# PCB-2x8GPIO.net
KiCad netlist of a schematic drawn in EAGLE
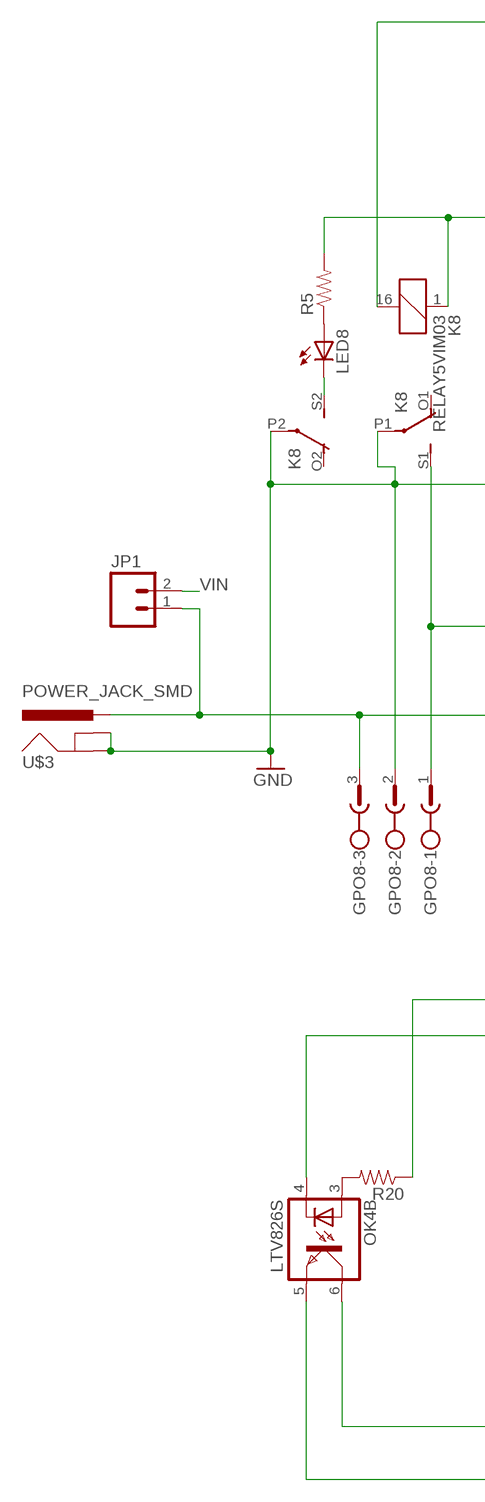
[diagram p0: schematic, sheet 1, part 1 of 2]
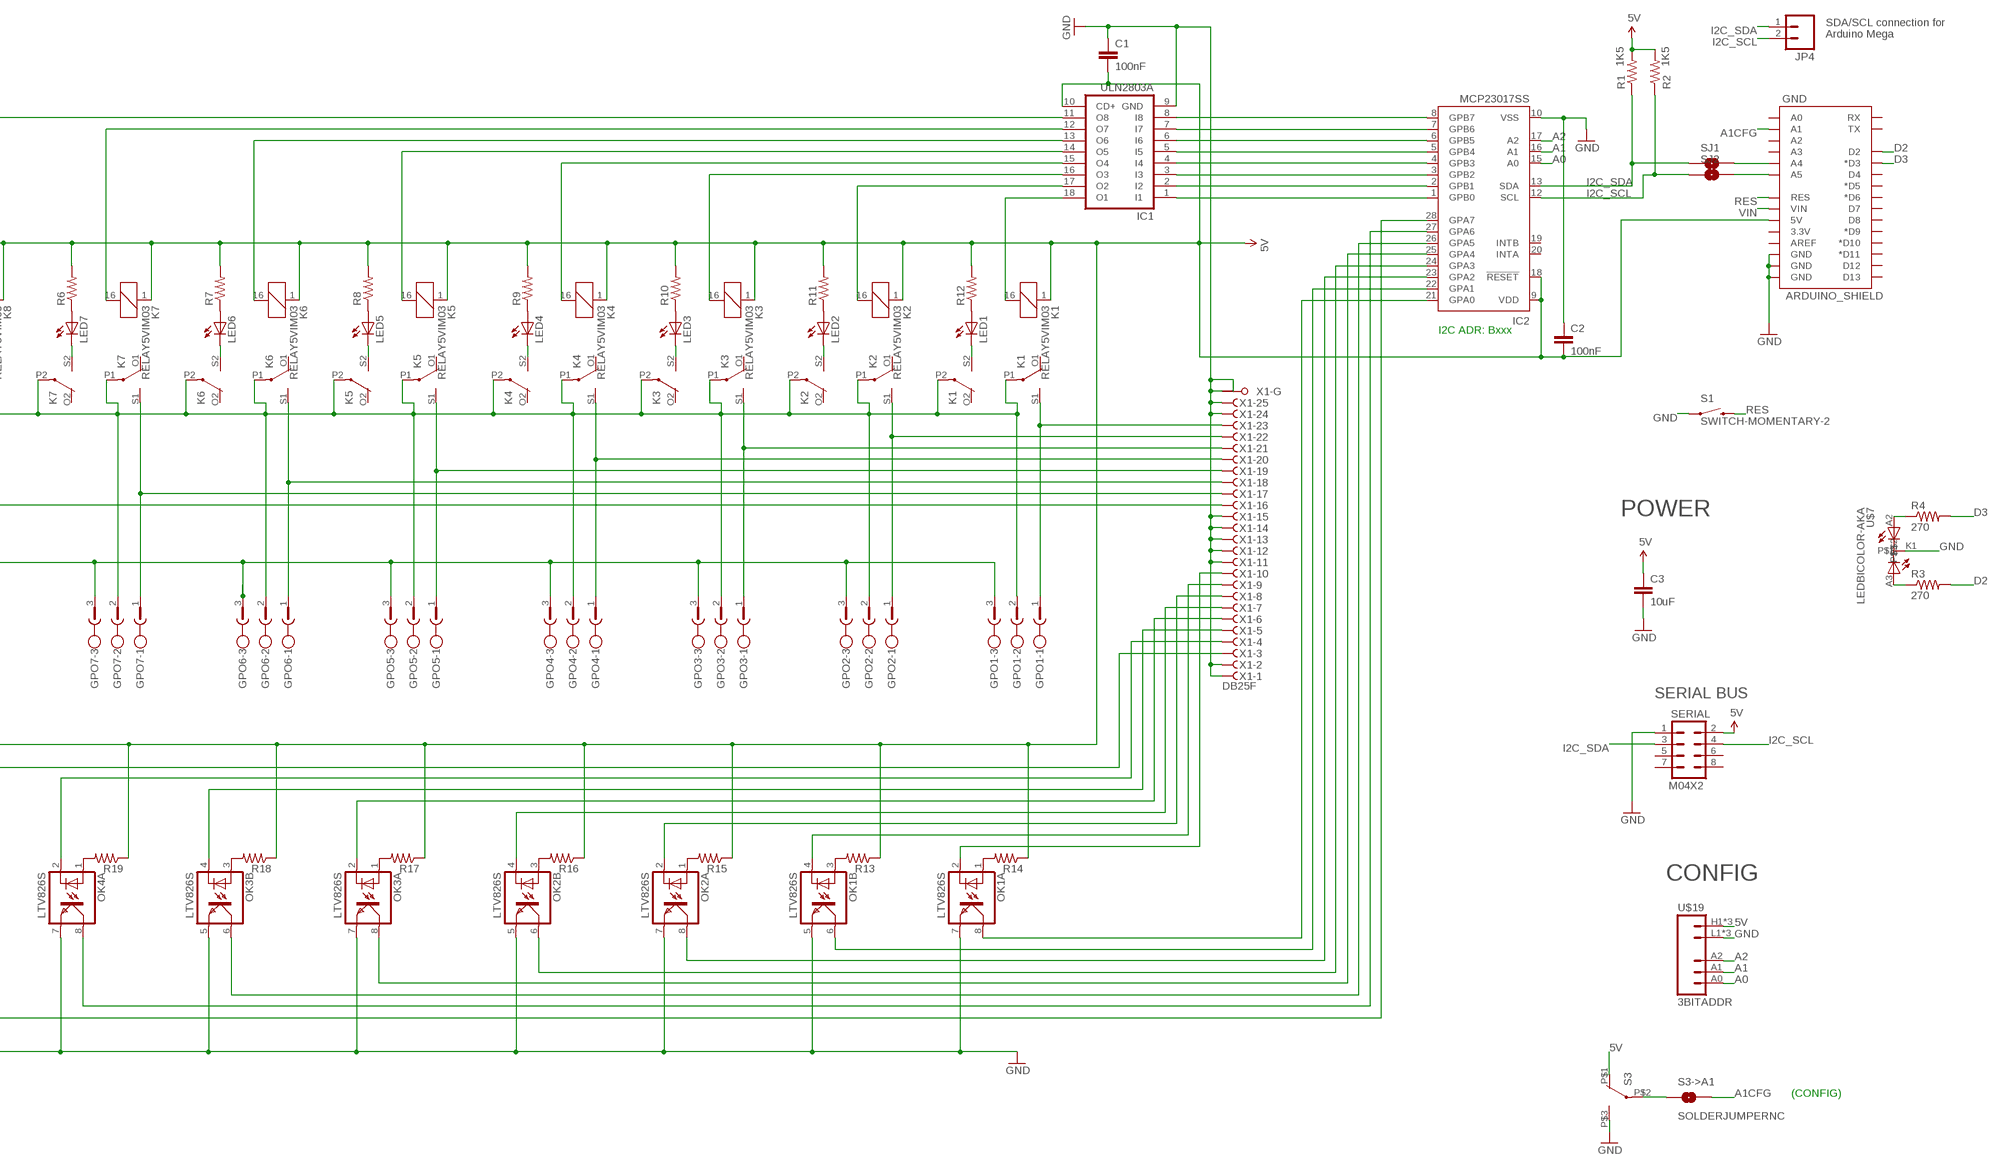
[diagram p1: schematic, sheet 1, part 2 of 2]

(export (version "E")
  (design (tool "Eeschema 10.0.6"))
  (components
    (comp (ref "C1")
      (value "100nF")
      (footprint "eagle-import:0805")
      (libsource (lib "eagle-import") (part "CAP0805"))
    )
    (comp (ref "C2")
      (value "100nF")
      (footprint "eagle-import:0603-CAP")
      (libsource (lib "eagle-import") (part "CAP0603-CAP"))
    )
    (comp (ref "C3")
      (value "10uF")
      (footprint "eagle-import:0805")
      (libsource (lib "eagle-import") (part "CAP0805"))
    )
    (comp (ref "GND")
      (value "ARDUINO_SHIELD")
      (footprint "eagle-import:ARDUINO_BOXSHIELD_NOHOLES")
      (libsource (lib "eagle-import") (part "ARDUINO_SHIELD"))
    )
    (comp (ref "GPO1")
      (value "CON1")
      (footprint "eagle-import:MSTBV3")
      (fields (field (name "MPN") "MSTBV 2,5/3-GF-5.08"))
      (libsource (lib "eagle-import") (part "MSTBV3"))
    )
    (comp (ref "GPO2")
      (value "CON1")
      (footprint "eagle-import:MSTBV3")
      (fields (field (name "MPN") "MSTBV 2,5/3-GF-5.08"))
      (libsource (lib "eagle-import") (part "MSTBV3"))
    )
    (comp (ref "GPO3")
      (value "CON1")
      (footprint "eagle-import:MSTBV3")
      (fields (field (name "MPN") "MSTBV 2,5/3-GF-5.08"))
      (libsource (lib "eagle-import") (part "MSTBV3"))
    )
    (comp (ref "GPO4")
      (value "CON1")
      (footprint "eagle-import:MSTBV3")
      (fields (field (name "MPN") "MSTBV 2,5/3-GF-5.08"))
      (libsource (lib "eagle-import") (part "MSTBV3"))
    )
    (comp (ref "GPO5")
      (value "CON1")
      (footprint "eagle-import:MSTBV3")
      (fields (field (name "MPN") "MSTBV 2,5/3-GF-5.08"))
      (libsource (lib "eagle-import") (part "MSTBV3"))
    )
    (comp (ref "GPO6")
      (value "CON1")
      (footprint "eagle-import:MSTBV3")
      (fields (field (name "MPN") "MSTBV 2,5/3-GF-5.08"))
      (libsource (lib "eagle-import") (part "MSTBV3"))
    )
    (comp (ref "GPO7")
      (value "CON1")
      (footprint "eagle-import:MSTBV3")
      (fields (field (name "MPN") "MSTBV 2,5/3-GF-5.08"))
      (libsource (lib "eagle-import") (part "MSTBV3"))
    )
    (comp (ref "GPO8")
      (value "GPO8")
      (footprint "eagle-import:MSTBV3")
      (fields (field (name "MPN") "MSTBV 2,5/3-GF-5.08"))
      (libsource (lib "eagle-import") (part "MSTBV3"))
    )
    (comp (ref "IC1")
      (value "ULN2803A")
      (footprint "eagle-import:SO18W")
      (libsource (lib "eagle-import") (part "ULN2803ASO18W"))
    )
    (comp (ref "IC2")
      (value "MCP23017SS")
      (footprint "eagle-import:SSOP28")
      (fields (field (name "MF") "MICROCHIP") (field (name "MPN") "MCP23017-E/SS"))
      (libsource (lib "eagle-import") (part "MCP23017SS"))
    )
    (comp (ref "JP1")
      (value "M02LOCK")
      (footprint "eagle-import:1X02_LOCK")
      (libsource (lib "eagle-import") (part "M02LOCK"))
    )
    (comp (ref "JP4")
      (value "M02PTH")
      (footprint "eagle-import:1X02")
      (libsource (lib "eagle-import") (part "M02PTH"))
    )
    (comp (ref "K1")
      (value "RELAY5VIM03")
      (footprint "eagle-import:DS2Y")
      (libsource (lib "eagle-import") (part "RELAY5VIM03"))
    )
    (comp (ref "K2")
      (value "RELAY5VIM03")
      (footprint "eagle-import:DS2Y")
      (libsource (lib "eagle-import") (part "RELAY5VIM03"))
    )
    (comp (ref "K3")
      (value "RELAY5VIM03")
      (footprint "eagle-import:DS2Y")
      (libsource (lib "eagle-import") (part "RELAY5VIM03"))
    )
    (comp (ref "K4")
      (value "RELAY5VIM03")
      (footprint "eagle-import:DS2Y")
      (libsource (lib "eagle-import") (part "RELAY5VIM03"))
    )
    (comp (ref "K5")
      (value "RELAY5VIM03")
      (footprint "eagle-import:DS2Y")
      (libsource (lib "eagle-import") (part "RELAY5VIM03"))
    )
    (comp (ref "K6")
      (value "RELAY5VIM03")
      (footprint "eagle-import:DS2Y")
      (libsource (lib "eagle-import") (part "RELAY5VIM03"))
    )
    (comp (ref "K7")
      (value "RELAY5VIM03")
      (footprint "eagle-import:DS2Y")
      (libsource (lib "eagle-import") (part "RELAY5VIM03"))
    )
    (comp (ref "K8")
      (value "RELAY5VIM03")
      (footprint "eagle-import:DS2Y")
      (libsource (lib "eagle-import") (part "RELAY5VIM03"))
    )
    (comp (ref "LED1")
      (value "LED0603")
      (footprint "eagle-import:LED-0603")
      (libsource (lib "eagle-import") (part "LED0603"))
    )
    (comp (ref "LED2")
      (value "LED0603")
      (footprint "eagle-import:LED-0603")
      (libsource (lib "eagle-import") (part "LED0603"))
    )
    (comp (ref "LED3")
      (value "LED0603")
      (footprint "eagle-import:LED-0603")
      (libsource (lib "eagle-import") (part "LED0603"))
    )
    (comp (ref "LED4")
      (value "LED0603")
      (footprint "eagle-import:LED-0603")
      (libsource (lib "eagle-import") (part "LED0603"))
    )
    (comp (ref "LED5")
      (value "LED0603")
      (footprint "eagle-import:LED-0603")
      (libsource (lib "eagle-import") (part "LED0603"))
    )
    (comp (ref "LED6")
      (value "LED0603")
      (footprint "eagle-import:LED-0603")
      (libsource (lib "eagle-import") (part "LED0603"))
    )
    (comp (ref "LED7")
      (value "LED0603")
      (footprint "eagle-import:LED-0603")
      (libsource (lib "eagle-import") (part "LED0603"))
    )
    (comp (ref "LED8")
      (value "LED0603")
      (footprint "eagle-import:LED-0603")
      (libsource (lib "eagle-import") (part "LED0603"))
    )
    (comp (ref "OK1")
      (value "LTV826S")
      (footprint "eagle-import:DIL8-SMD")
      (libsource (lib "eagle-import") (part "LTV826S"))
    )
    (comp (ref "OK2")
      (value "LTV826S")
      (footprint "eagle-import:DIL8-SMD")
      (libsource (lib "eagle-import") (part "LTV826S"))
    )
    (comp (ref "OK3")
      (value "LTV826S")
      (footprint "eagle-import:DIL8-SMD")
      (libsource (lib "eagle-import") (part "LTV826S"))
    )
    (comp (ref "OK4")
      (value "LTV826S")
      (footprint "eagle-import:DIL8-SMD")
      (libsource (lib "eagle-import") (part "LTV826S"))
    )
    (comp (ref "R1")
      (value "1K5")
      (footprint "eagle-import:0603-RES")
      (libsource (lib "eagle-import") (part "RESISTOR0603-RES"))
    )
    (comp (ref "R2")
      (value "1K5")
      (footprint "eagle-import:0603-RES")
      (libsource (lib "eagle-import") (part "RESISTOR0603-RES"))
    )
    (comp (ref "R3")
      (value "270")
      (footprint "eagle-import:0603-RES")
      (libsource (lib "eagle-import") (part "RESISTOR0603-RES"))
    )
    (comp (ref "R4")
      (value "270")
      (footprint "eagle-import:0603-RES")
      (libsource (lib "eagle-import") (part "RESISTOR0603-RES"))
    )
    (comp (ref "R5")
      (value "RESISTOR0603-RES")
      (footprint "eagle-import:0603-RES")
      (libsource (lib "eagle-import") (part "RESISTOR0603-RES"))
    )
    (comp (ref "R6")
      (value "RESISTOR0603-RES")
      (footprint "eagle-import:0603-RES")
      (libsource (lib "eagle-import") (part "RESISTOR0603-RES"))
    )
    (comp (ref "R7")
      (value "RESISTOR0603-RES")
      (footprint "eagle-import:0603-RES")
      (libsource (lib "eagle-import") (part "RESISTOR0603-RES"))
    )
    (comp (ref "R8")
      (value "RESISTOR0603-RES")
      (footprint "eagle-import:0603-RES")
      (libsource (lib "eagle-import") (part "RESISTOR0603-RES"))
    )
    (comp (ref "R9")
      (value "RESISTOR0603-RES")
      (footprint "eagle-import:0603-RES")
      (libsource (lib "eagle-import") (part "RESISTOR0603-RES"))
    )
    (comp (ref "R10")
      (value "RESISTOR0603-RES")
      (footprint "eagle-import:0603-RES")
      (libsource (lib "eagle-import") (part "RESISTOR0603-RES"))
    )
    (comp (ref "R11")
      (value "RESISTOR0603-RES")
      (footprint "eagle-import:0603-RES")
      (libsource (lib "eagle-import") (part "RESISTOR0603-RES"))
    )
    (comp (ref "R12")
      (value "RESISTOR0603-RES")
      (footprint "eagle-import:0603-RES")
      (libsource (lib "eagle-import") (part "RESISTOR0603-RES"))
    )
    (comp (ref "R13")
      (value "RESISTOR0603-RES")
      (footprint "eagle-import:0603-RES")
      (libsource (lib "eagle-import") (part "RESISTOR0603-RES"))
    )
    (comp (ref "R14")
      (value "RESISTOR0603-RES")
      (footprint "eagle-import:0603-RES")
      (libsource (lib "eagle-import") (part "RESISTOR0603-RES"))
    )
    (comp (ref "R15")
      (value "RESISTOR0603-RES")
      (footprint "eagle-import:0603-RES")
      (libsource (lib "eagle-import") (part "RESISTOR0603-RES"))
    )
    (comp (ref "R16")
      (value "RESISTOR0603-RES")
      (footprint "eagle-import:0603-RES")
      (libsource (lib "eagle-import") (part "RESISTOR0603-RES"))
    )
    (comp (ref "R17")
      (value "RESISTOR0603-RES")
      (footprint "eagle-import:0603-RES")
      (libsource (lib "eagle-import") (part "RESISTOR0603-RES"))
    )
    (comp (ref "R18")
      (value "RESISTOR0603-RES")
      (footprint "eagle-import:0603-RES")
      (libsource (lib "eagle-import") (part "RESISTOR0603-RES"))
    )
    (comp (ref "R19")
      (value "RESISTOR0603-RES")
      (footprint "eagle-import:0603-RES")
      (libsource (lib "eagle-import") (part "RESISTOR0603-RES"))
    )
    (comp (ref "R20")
      (value "RESISTOR0603-RES")
      (footprint "eagle-import:0603-RES")
      (libsource (lib "eagle-import") (part "RESISTOR0603-RES"))
    )
    (comp (ref "S1")
      (value "SWITCH-MOMENTARY-2")
      (footprint "eagle-import:TACTILE_SWITCH_TALL")
      (libsource (lib "eagle-import") (part "SWITCH-MOMENTARY-2"))
    )
    (comp (ref "S3")
      (value "CFG")
      (footprint "eagle-import:TECONNECTIVITY-DPST")
      (libsource (lib "eagle-import") (part "SWITCH-DPST"))
    )
    (comp (ref "S3->A1")
      (value "SOLDERJUMPERNC")
      (footprint "eagle-import:SJ_2S")
      (libsource (lib "eagle-import") (part "SOLDERJUMPERNC"))
    )
    (comp (ref "SERIAL")
      (value "M04X2")
      (footprint "eagle-import:2X4")
      (libsource (lib "eagle-import") (part "M04X2"))
    )
    (comp (ref "SJ1")
      (value "SOLDERJUMPERNC")
      (footprint "eagle-import:SJ_2S")
      (libsource (lib "eagle-import") (part "SOLDERJUMPERNC"))
    )
    (comp (ref "SJ2")
      (value "SOLDERJUMPERNC")
      (footprint "eagle-import:SJ_2S")
      (libsource (lib "eagle-import") (part "SOLDERJUMPERNC"))
    )
    (comp (ref "U$3")
      (value "POWER_JACK_SMD")
      (footprint "eagle-import:POWER_JACK_SMD")
      (libsource (lib "eagle-import") (part "POWER_JACK_SMD"))
    )
    (comp (ref "U$7")
      (value "LEDBICOLOR-AKA")
      (footprint "eagle-import:LED5MM-BICOLOR")
      (libsource (lib "eagle-import") (part "LEDBICOLOR-AKA"))
    )
    (comp (ref "U$19")
      (value "3BITADDR")
      (footprint "eagle-import:3BITADDR")
      (libsource (lib "eagle-import") (part "3BITADDR"))
    )
    (comp (ref "X1")
      (value "DB25F")
      (footprint "eagle-import:F25HP")
      (libsource (lib "eagle-import") (part "F25HPS"))
    )
  )
  (nets
    (net (code "1") (name "/A0") (class "Default")
      (node (ref "IC2") (pin "15") (pinfunction "A0_15") (pintype "input"))
      (node (ref "U$19") (pin "A0") (pinfunction "A0_A0") (pintype "passive"))
    )
    (net (code "2") (name "/A1") (class "Default")
      (node (ref "IC2") (pin "16") (pinfunction "A1_16") (pintype "input"))
      (node (ref "U$19") (pin "A1") (pinfunction "A1_A1") (pintype "passive"))
    )
    (net (code "3") (name "/A1CFG") (class "Default")
      (node (ref "GND") (pin "A1") (pinfunction "A1_A1") (pintype "bidirectional"))
      (node (ref "S3->A1") (pin "2") (pinfunction "2_2") (pintype "passive"))
    )
    (net (code "4") (name "/A2") (class "Default")
      (node (ref "IC2") (pin "17") (pinfunction "A2_17") (pintype "input"))
      (node (ref "U$19") (pin "A2") (pinfunction "A2_A2") (pintype "passive"))
    )
    (net (code "5") (name "/D2") (class "Default")
      (node (ref "GND") (pin "2") (pinfunction "D2_2") (pintype "bidirectional"))
      (node (ref "R3") (pin "2") (pinfunction "2_2") (pintype "passive"))
    )
    (net (code "6") (name "/D3") (class "Default")
      (node (ref "GND") (pin "3") (pinfunction "*D3_3") (pintype "bidirectional"))
      (node (ref "R4") (pin "2") (pinfunction "2_2") (pintype "passive"))
    )
    (net (code "7") (name "/I2C_SCL") (class "Default")
      (node (ref "IC2") (pin "12") (pinfunction "SCL_12") (pintype "input"))
      (node (ref "JP4") (pin "2") (pinfunction "2_2") (pintype "passive"))
      (node (ref "R2") (pin "1") (pinfunction "1_1") (pintype "passive"))
      (node (ref "SERIAL") (pin "4") (pinfunction "4_4") (pintype "passive"))
      (node (ref "SJ2") (pin "1") (pinfunction "1_1") (pintype "passive"))
    )
    (net (code "8") (name "/I2C_SDA") (class "Default")
      (node (ref "IC2") (pin "13") (pinfunction "SDA_13") (pintype "bidirectional"))
      (node (ref "JP4") (pin "1") (pinfunction "1_1") (pintype "passive"))
      (node (ref "R1") (pin "1") (pinfunction "1_1") (pintype "passive"))
      (node (ref "SERIAL") (pin "3") (pinfunction "3_3") (pintype "passive"))
      (node (ref "SJ1") (pin "1") (pinfunction "1_1") (pintype "passive"))
    )
    (net (code "9") (name "/RES") (class "Default")
      (node (ref "GND") (pin "RESET") (pinfunction "RES_RESET") (pintype "bidirectional"))
      (node (ref "S1") (pin "B2") (pinfunction "2_B2") (pintype "passive"))
    )
    (net (code "10") (name "/VIN") (class "Default")
      (node (ref "GND") (pin "VIN") (pinfunction "VIN_VIN") (pintype "bidirectional"))
      (node (ref "JP1") (pin "2") (pinfunction "2_2") (pintype "passive"))
    )
    (net (code "11") (name "5V") (class "Default")
      (node (ref "C1") (pin "2") (pinfunction "2_2") (pintype "passive"))
      (node (ref "C2") (pin "2") (pinfunction "2_2") (pintype "passive"))
      (node (ref "C3") (pin "1") (pinfunction "1_1") (pintype "passive"))
      (node (ref "GND") (pin "5V@0") (pinfunction "5V_5V@0") (pintype "bidirectional"))
      (node (ref "IC1") (pin "10") (pinfunction "CD+_10") (pintype "passive"))
      (node (ref "IC2") (pin "18") (pinfunction "~{RESET}_18") (pintype "input"))
      (node (ref "IC2") (pin "9") (pinfunction "VDD_9") (pintype "power_in"))
      (node (ref "K1") (pin "1") (pinfunction "1_1") (pintype "passive"))
      (node (ref "K2") (pin "1") (pinfunction "1_1") (pintype "passive"))
      (node (ref "K3") (pin "1") (pinfunction "1_1") (pintype "passive"))
      (node (ref "K4") (pin "1") (pinfunction "1_1") (pintype "passive"))
      (node (ref "K5") (pin "1") (pinfunction "1_1") (pintype "passive"))
      (node (ref "K6") (pin "1") (pinfunction "1_1") (pintype "passive"))
      (node (ref "K7") (pin "1") (pinfunction "1_1") (pintype "passive"))
      (node (ref "K8") (pin "1") (pinfunction "1_1") (pintype "passive"))
      (node (ref "R1") (pin "2") (pinfunction "2_2") (pintype "passive"))
      (node (ref "R10") (pin "2") (pinfunction "2_2") (pintype "passive"))
      (node (ref "R11") (pin "2") (pinfunction "2_2") (pintype "passive"))
      (node (ref "R12") (pin "2") (pinfunction "2_2") (pintype "passive"))
      (node (ref "R13") (pin "1") (pinfunction "1_1") (pintype "passive"))
      (node (ref "R14") (pin "1") (pinfunction "1_1") (pintype "passive"))
      (node (ref "R15") (pin "1") (pinfunction "1_1") (pintype "passive"))
      (node (ref "R16") (pin "1") (pinfunction "1_1") (pintype "passive"))
      (node (ref "R17") (pin "1") (pinfunction "1_1") (pintype "passive"))
      (node (ref "R18") (pin "1") (pinfunction "1_1") (pintype "passive"))
      (node (ref "R19") (pin "1") (pinfunction "1_1") (pintype "passive"))
      (node (ref "R2") (pin "2") (pinfunction "2_2") (pintype "passive"))
      (node (ref "R20") (pin "1") (pinfunction "1_1") (pintype "passive"))
      (node (ref "R5") (pin "2") (pinfunction "2_2") (pintype "passive"))
      (node (ref "R6") (pin "2") (pinfunction "2_2") (pintype "passive"))
      (node (ref "R7") (pin "2") (pinfunction "2_2") (pintype "passive"))
      (node (ref "R8") (pin "2") (pinfunction "2_2") (pintype "passive"))
      (node (ref "R9") (pin "2") (pinfunction "2_2") (pintype "passive"))
      (node (ref "S3") (pin "P$1") (pinfunction "O_P$1") (pintype "passive"))
      (node (ref "SERIAL") (pin "2") (pinfunction "2_2") (pintype "passive"))
      (node (ref "U$19") (pin "H1") (pinfunction "VCC_H1") (pintype "passive"))
      (node (ref "U$19") (pin "H2") (pinfunction "VCC_H2") (pintype "passive"))
      (node (ref "U$19") (pin "H3") (pinfunction "VCC_H3") (pintype "passive"))
    )
    (net (code "12") (name "GND") (class "Default")
      (node (ref "C1") (pin "1") (pinfunction "1_1") (pintype "passive"))
      (node (ref "C2") (pin "1") (pinfunction "1_1") (pintype "passive"))
      (node (ref "C3") (pin "2") (pinfunction "2_2") (pintype "passive"))
      (node (ref "GND") (pin "GND@0") (pinfunction "GND_GND@0") (pintype "bidirectional"))
      (node (ref "GND") (pin "GND@1") (pinfunction "GND_GND@1") (pintype "bidirectional"))
      (node (ref "GND") (pin "GND@4") (pinfunction "GND_GND@4") (pintype "bidirectional"))
      (node (ref "GPO1") (pin "2") (pinfunction "1_2") (pintype "passive"))
      (node (ref "GPO2") (pin "2") (pinfunction "1_2") (pintype "passive"))
      (node (ref "GPO3") (pin "2") (pinfunction "1_2") (pintype "passive"))
      (node (ref "GPO4") (pin "2") (pinfunction "1_2") (pintype "passive"))
      (node (ref "GPO5") (pin "2") (pinfunction "1_2") (pintype "passive"))
      (node (ref "GPO6") (pin "2") (pinfunction "1_2") (pintype "passive"))
      (node (ref "GPO7") (pin "2") (pinfunction "1_2") (pintype "passive"))
      (node (ref "GPO8") (pin "2") (pinfunction "1_2") (pintype "passive"))
      (node (ref "IC1") (pin "9") (pinfunction "GND_9") (pintype "power_in"))
      (node (ref "IC2") (pin "10") (pinfunction "VSS_10") (pintype "power_in"))
      (node (ref "K1") (pin "P1") (pinfunction "P_P1") (pintype "passive"))
      (node (ref "K1") (pin "P2") (pinfunction "P_P2") (pintype "passive"))
      (node (ref "K2") (pin "P1") (pinfunction "P_P1") (pintype "passive"))
      (node (ref "K2") (pin "P2") (pinfunction "P_P2") (pintype "passive"))
      (node (ref "K3") (pin "P1") (pinfunction "P_P1") (pintype "passive"))
      (node (ref "K3") (pin "P2") (pinfunction "P_P2") (pintype "passive"))
      (node (ref "K4") (pin "P1") (pinfunction "P_P1") (pintype "passive"))
      (node (ref "K4") (pin "P2") (pinfunction "P_P2") (pintype "passive"))
      (node (ref "K5") (pin "P1") (pinfunction "P_P1") (pintype "passive"))
      (node (ref "K5") (pin "P2") (pinfunction "P_P2") (pintype "passive"))
      (node (ref "K6") (pin "P1") (pinfunction "P_P1") (pintype "passive"))
      (node (ref "K6") (pin "P2") (pinfunction "P_P2") (pintype "passive"))
      (node (ref "K7") (pin "P1") (pinfunction "P_P1") (pintype "passive"))
      (node (ref "K7") (pin "P2") (pinfunction "P_P2") (pintype "passive"))
      (node (ref "K8") (pin "P1") (pinfunction "P_P1") (pintype "passive"))
      (node (ref "K8") (pin "P2") (pinfunction "P_P2") (pintype "passive"))
      (node (ref "OK1") (pin "5") (pinfunction "EMIT_5") (pintype "passive"))
      (node (ref "OK1") (pin "7") (pinfunction "EMIT_7") (pintype "passive"))
      (node (ref "OK2") (pin "5") (pinfunction "EMIT_5") (pintype "passive"))
      (node (ref "OK2") (pin "7") (pinfunction "EMIT_7") (pintype "passive"))
      (node (ref "OK3") (pin "5") (pinfunction "EMIT_5") (pintype "passive"))
      (node (ref "OK3") (pin "7") (pinfunction "EMIT_7") (pintype "passive"))
      (node (ref "OK4") (pin "5") (pinfunction "EMIT_5") (pintype "passive"))
      (node (ref "OK4") (pin "7") (pinfunction "EMIT_7") (pintype "passive"))
      (node (ref "S1") (pin "A2") (pinfunction "1_A2") (pintype "passive"))
      (node (ref "S3") (pin "P$3") (pinfunction "S_P$3") (pintype "passive"))
      (node (ref "SERIAL") (pin "1") (pinfunction "1_1") (pintype "passive"))
      (node (ref "U$19") (pin "L1") (pinfunction "GND_L1") (pintype "passive"))
      (node (ref "U$19") (pin "L2") (pinfunction "GND_L2") (pintype "passive"))
      (node (ref "U$19") (pin "L3") (pinfunction "GND_L3") (pintype "passive"))
      (node (ref "U$3") (pin "GND") (pinfunction "GND_GND") (pintype "bidirectional"))
      (node (ref "U$3") (pin "SHUNT") (pinfunction "GNDBREAK_SHUNT") (pintype "bidirectional"))
      (node (ref "U$7") (pin "K1") (pinfunction "P$1_K1") (pintype "bidirectional"))
      (node (ref "X1") (pin "1") (pinfunction "F_1") (pintype "passive"))
      (node (ref "X1") (pin "11") (pinfunction "F_11") (pintype "passive"))
      (node (ref "X1") (pin "12") (pinfunction "F_12") (pintype "passive"))
      (node (ref "X1") (pin "13") (pinfunction "F_13") (pintype "passive"))
      (node (ref "X1") (pin "14") (pinfunction "F_14") (pintype "passive"))
      (node (ref "X1") (pin "15") (pinfunction "F_15") (pintype "passive"))
      (node (ref "X1") (pin "2") (pinfunction "F_2") (pintype "passive"))
      (node (ref "X1") (pin "24") (pinfunction "F_24") (pintype "passive"))
      (node (ref "X1") (pin "25") (pinfunction "F_25") (pintype "passive"))
      (node (ref "X1") (pin "G1") (pinfunction "G1_G1") (pintype "passive"))
      (node (ref "X1") (pin "G2") (pinfunction "G2_G2") (pintype "passive"))
    )
    (net (code "13") (name "Net-(GND-PadA4)") (class "Default")
      (node (ref "GND") (pin "A4") (pinfunction "A4_A4") (pintype "bidirectional"))
      (node (ref "SJ1") (pin "2") (pinfunction "2_2") (pintype "passive"))
    )
    (net (code "14") (name "Net-(GND-PadA5)") (class "Default")
      (node (ref "GND") (pin "A5") (pinfunction "A5_A5") (pintype "bidirectional"))
      (node (ref "SJ2") (pin "2") (pinfunction "2_2") (pintype "passive"))
    )
    (net (code "15") (name "Net-(GPO1C-1)") (class "Default")
      (node (ref "GPO1") (pin "3") (pinfunction "1_3") (pintype "passive"))
      (node (ref "GPO2") (pin "3") (pinfunction "1_3") (pintype "passive"))
      (node (ref "GPO3") (pin "3") (pinfunction "1_3") (pintype "passive"))
      (node (ref "GPO4") (pin "3") (pinfunction "1_3") (pintype "passive"))
      (node (ref "GPO5") (pin "3") (pinfunction "1_3") (pintype "passive"))
      (node (ref "GPO6") (pin "3") (pinfunction "1_3") (pintype "passive"))
      (node (ref "GPO7") (pin "3") (pinfunction "1_3") (pintype "passive"))
      (node (ref "GPO8") (pin "3") (pinfunction "1_3") (pintype "passive"))
      (node (ref "JP1") (pin "1") (pinfunction "1_1") (pintype "passive"))
      (node (ref "U$3") (pin "PWR") (pinfunction "PWR_PWR") (pintype "bidirectional"))
    )
    (net (code "16") (name "Net-(IC1-I1)") (class "Default")
      (node (ref "IC1") (pin "1") (pinfunction "I1_1") (pintype "input"))
      (node (ref "IC2") (pin "1") (pinfunction "GPB0_1") (pintype "bidirectional"))
    )
    (net (code "17") (name "Net-(IC1-I2)") (class "Default")
      (node (ref "IC1") (pin "2") (pinfunction "I2_2") (pintype "input"))
      (node (ref "IC2") (pin "2") (pinfunction "GPB1_2") (pintype "bidirectional"))
    )
    (net (code "18") (name "Net-(IC1-I3)") (class "Default")
      (node (ref "IC1") (pin "3") (pinfunction "I3_3") (pintype "input"))
      (node (ref "IC2") (pin "3") (pinfunction "GPB2_3") (pintype "bidirectional"))
    )
    (net (code "19") (name "Net-(IC1-I4)") (class "Default")
      (node (ref "IC1") (pin "4") (pinfunction "I4_4") (pintype "input"))
      (node (ref "IC2") (pin "4") (pinfunction "GPB3_4") (pintype "bidirectional"))
    )
    (net (code "20") (name "Net-(IC1-I5)") (class "Default")
      (node (ref "IC1") (pin "5") (pinfunction "I5_5") (pintype "input"))
      (node (ref "IC2") (pin "5") (pinfunction "GPB4_5") (pintype "bidirectional"))
    )
    (net (code "21") (name "Net-(IC1-I6)") (class "Default")
      (node (ref "IC1") (pin "6") (pinfunction "I6_6") (pintype "input"))
      (node (ref "IC2") (pin "6") (pinfunction "GPB5_6") (pintype "bidirectional"))
    )
    (net (code "22") (name "Net-(IC1-I7)") (class "Default")
      (node (ref "IC1") (pin "7") (pinfunction "I7_7") (pintype "input"))
      (node (ref "IC2") (pin "7") (pinfunction "GPB6_7") (pintype "bidirectional"))
    )
    (net (code "23") (name "Net-(IC1-I8)") (class "Default")
      (node (ref "IC1") (pin "8") (pinfunction "I8_8") (pintype "input"))
      (node (ref "IC2") (pin "8") (pinfunction "GPB7_8") (pintype "bidirectional"))
    )
    (net (code "24") (name "Net-(IC1-O1)") (class "Default")
      (node (ref "IC1") (pin "18") (pinfunction "O1_18") (pintype "open_collector"))
      (node (ref "K1") (pin "16") (pinfunction "2_16") (pintype "passive"))
    )
    (net (code "25") (name "Net-(IC1-O2)") (class "Default")
      (node (ref "IC1") (pin "17") (pinfunction "O2_17") (pintype "open_collector"))
      (node (ref "K2") (pin "16") (pinfunction "2_16") (pintype "passive"))
    )
    (net (code "26") (name "Net-(IC1-O3)") (class "Default")
      (node (ref "IC1") (pin "16") (pinfunction "O3_16") (pintype "open_collector"))
      (node (ref "K3") (pin "16") (pinfunction "2_16") (pintype "passive"))
    )
    (net (code "27") (name "Net-(IC1-O4)") (class "Default")
      (node (ref "IC1") (pin "15") (pinfunction "O4_15") (pintype "open_collector"))
      (node (ref "K4") (pin "16") (pinfunction "2_16") (pintype "passive"))
    )
    (net (code "28") (name "Net-(IC1-O5)") (class "Default")
      (node (ref "IC1") (pin "14") (pinfunction "O5_14") (pintype "open_collector"))
      (node (ref "K5") (pin "16") (pinfunction "2_16") (pintype "passive"))
    )
    (net (code "29") (name "Net-(IC1-O6)") (class "Default")
      (node (ref "IC1") (pin "13") (pinfunction "O6_13") (pintype "open_collector"))
      (node (ref "K6") (pin "16") (pinfunction "2_16") (pintype "passive"))
    )
    (net (code "30") (name "Net-(IC1-O7)") (class "Default")
      (node (ref "IC1") (pin "12") (pinfunction "O7_12") (pintype "open_collector"))
      (node (ref "K7") (pin "16") (pinfunction "2_16") (pintype "passive"))
    )
    (net (code "31") (name "Net-(IC1-O8)") (class "Default")
      (node (ref "IC1") (pin "11") (pinfunction "O8_11") (pintype "open_collector"))
      (node (ref "K8") (pin "16") (pinfunction "2_16") (pintype "passive"))
    )
    (net (code "32") (name "Net-(IC2-GPA0)") (class "Default")
      (node (ref "IC2") (pin "21") (pinfunction "GPA0_21") (pintype "bidirectional"))
      (node (ref "OK1") (pin "8") (pinfunction "COL_8") (pintype "passive"))
    )
    (net (code "33") (name "Net-(IC2-GPA1)") (class "Default")
      (node (ref "IC2") (pin "22") (pinfunction "GPA1_22") (pintype "bidirectional"))
      (node (ref "OK1") (pin "6") (pinfunction "COL_6") (pintype "passive"))
    )
    (net (code "34") (name "Net-(IC2-GPA2)") (class "Default")
      (node (ref "IC2") (pin "23") (pinfunction "GPA2_23") (pintype "bidirectional"))
      (node (ref "OK2") (pin "8") (pinfunction "COL_8") (pintype "passive"))
    )
    (net (code "35") (name "Net-(IC2-GPA3)") (class "Default")
      (node (ref "IC2") (pin "24") (pinfunction "GPA3_24") (pintype "bidirectional"))
      (node (ref "OK2") (pin "6") (pinfunction "COL_6") (pintype "passive"))
    )
    (net (code "36") (name "Net-(IC2-GPA4)") (class "Default")
      (node (ref "IC2") (pin "25") (pinfunction "GPA4_25") (pintype "bidirectional"))
      (node (ref "OK3") (pin "8") (pinfunction "COL_8") (pintype "passive"))
    )
    (net (code "37") (name "Net-(IC2-GPA5)") (class "Default")
      (node (ref "IC2") (pin "26") (pinfunction "GPA5_26") (pintype "bidirectional"))
      (node (ref "OK3") (pin "6") (pinfunction "COL_6") (pintype "passive"))
    )
    (net (code "38") (name "Net-(IC2-GPA6)") (class "Default")
      (node (ref "IC2") (pin "27") (pinfunction "GPA6_27") (pintype "bidirectional"))
      (node (ref "OK4") (pin "8") (pinfunction "COL_8") (pintype "passive"))
    )
    (net (code "39") (name "Net-(IC2-GPA7)") (class "Default")
      (node (ref "IC2") (pin "28") (pinfunction "GPA7_28") (pintype "bidirectional"))
      (node (ref "OK4") (pin "6") (pinfunction "COL_6") (pintype "passive"))
    )
    (net (code "40") (name "Net-(K1B-S)") (class "Default")
      (node (ref "GPO1") (pin "1") (pinfunction "1_1") (pintype "passive"))
      (node (ref "K1") (pin "S1") (pinfunction "S_S1") (pintype "passive"))
      (node (ref "X1") (pin "23") (pinfunction "F_23") (pintype "passive"))
    )
    (net (code "41") (name "Net-(K1C-S)") (class "Default")
      (node (ref "K1") (pin "S2") (pinfunction "S_S2") (pintype "passive"))
      (node (ref "LED1") (pin "C") (pinfunction "C_C") (pintype "passive"))
    )
    (net (code "42") (name "Net-(K2B-S)") (class "Default")
      (node (ref "GPO2") (pin "1") (pinfunction "1_1") (pintype "passive"))
      (node (ref "K2") (pin "S1") (pinfunction "S_S1") (pintype "passive"))
      (node (ref "X1") (pin "22") (pinfunction "F_22") (pintype "passive"))
    )
    (net (code "43") (name "Net-(K2C-S)") (class "Default")
      (node (ref "K2") (pin "S2") (pinfunction "S_S2") (pintype "passive"))
      (node (ref "LED2") (pin "C") (pinfunction "C_C") (pintype "passive"))
    )
    (net (code "44") (name "Net-(K3B-S)") (class "Default")
      (node (ref "GPO3") (pin "1") (pinfunction "1_1") (pintype "passive"))
      (node (ref "K3") (pin "S1") (pinfunction "S_S1") (pintype "passive"))
      (node (ref "X1") (pin "21") (pinfunction "F_21") (pintype "passive"))
    )
    (net (code "45") (name "Net-(K3C-S)") (class "Default")
      (node (ref "K3") (pin "S2") (pinfunction "S_S2") (pintype "passive"))
      (node (ref "LED3") (pin "C") (pinfunction "C_C") (pintype "passive"))
    )
    (net (code "46") (name "Net-(K4B-S)") (class "Default")
      (node (ref "GPO4") (pin "1") (pinfunction "1_1") (pintype "passive"))
      (node (ref "K4") (pin "S1") (pinfunction "S_S1") (pintype "passive"))
      (node (ref "X1") (pin "20") (pinfunction "F_20") (pintype "passive"))
    )
    (net (code "47") (name "Net-(K4C-S)") (class "Default")
      (node (ref "K4") (pin "S2") (pinfunction "S_S2") (pintype "passive"))
      (node (ref "LED4") (pin "C") (pinfunction "C_C") (pintype "passive"))
    )
    (net (code "48") (name "Net-(K5B-S)") (class "Default")
      (node (ref "GPO5") (pin "1") (pinfunction "1_1") (pintype "passive"))
      (node (ref "K5") (pin "S1") (pinfunction "S_S1") (pintype "passive"))
      (node (ref "X1") (pin "19") (pinfunction "F_19") (pintype "passive"))
    )
    (net (code "49") (name "Net-(K5C-S)") (class "Default")
      (node (ref "K5") (pin "S2") (pinfunction "S_S2") (pintype "passive"))
      (node (ref "LED5") (pin "C") (pinfunction "C_C") (pintype "passive"))
    )
    (net (code "50") (name "Net-(K6B-S)") (class "Default")
      (node (ref "GPO6") (pin "1") (pinfunction "1_1") (pintype "passive"))
      (node (ref "K6") (pin "S1") (pinfunction "S_S1") (pintype "passive"))
      (node (ref "X1") (pin "18") (pinfunction "F_18") (pintype "passive"))
    )
    (net (code "51") (name "Net-(K6C-S)") (class "Default")
      (node (ref "K6") (pin "S2") (pinfunction "S_S2") (pintype "passive"))
      (node (ref "LED6") (pin "C") (pinfunction "C_C") (pintype "passive"))
    )
    (net (code "52") (name "Net-(K7B-S)") (class "Default")
      (node (ref "GPO7") (pin "1") (pinfunction "1_1") (pintype "passive"))
      (node (ref "K7") (pin "S1") (pinfunction "S_S1") (pintype "passive"))
      (node (ref "X1") (pin "17") (pinfunction "F_17") (pintype "passive"))
    )
    (net (code "53") (name "Net-(K7C-S)") (class "Default")
      (node (ref "K7") (pin "S2") (pinfunction "S_S2") (pintype "passive"))
      (node (ref "LED7") (pin "C") (pinfunction "C_C") (pintype "passive"))
    )
    (net (code "54") (name "Net-(K8B-S)") (class "Default")
      (node (ref "GPO8") (pin "1") (pinfunction "1_1") (pintype "passive"))
      (node (ref "K8") (pin "S1") (pinfunction "S_S1") (pintype "passive"))
      (node (ref "X1") (pin "16") (pinfunction "F_16") (pintype "passive"))
    )
    (net (code "55") (name "Net-(K8C-S)") (class "Default")
      (node (ref "K8") (pin "S2") (pinfunction "S_S2") (pintype "passive"))
      (node (ref "LED8") (pin "C") (pinfunction "C_C") (pintype "passive"))
    )
    (net (code "56") (name "Net-(LED1-PadA)") (class "Default")
      (node (ref "LED1") (pin "A") (pinfunction "A_A") (pintype "passive"))
      (node (ref "R12") (pin "1") (pinfunction "1_1") (pintype "passive"))
    )
    (net (code "57") (name "Net-(LED2-PadA)") (class "Default")
      (node (ref "LED2") (pin "A") (pinfunction "A_A") (pintype "passive"))
      (node (ref "R11") (pin "1") (pinfunction "1_1") (pintype "passive"))
    )
    (net (code "58") (name "Net-(LED3-PadA)") (class "Default")
      (node (ref "LED3") (pin "A") (pinfunction "A_A") (pintype "passive"))
      (node (ref "R10") (pin "1") (pinfunction "1_1") (pintype "passive"))
    )
    (net (code "59") (name "Net-(LED4-PadA)") (class "Default")
      (node (ref "LED4") (pin "A") (pinfunction "A_A") (pintype "passive"))
      (node (ref "R9") (pin "1") (pinfunction "1_1") (pintype "passive"))
    )
    (net (code "60") (name "Net-(LED5-PadA)") (class "Default")
      (node (ref "LED5") (pin "A") (pinfunction "A_A") (pintype "passive"))
      (node (ref "R8") (pin "1") (pinfunction "1_1") (pintype "passive"))
    )
    (net (code "61") (name "Net-(LED6-PadA)") (class "Default")
      (node (ref "LED6") (pin "A") (pinfunction "A_A") (pintype "passive"))
      (node (ref "R7") (pin "1") (pinfunction "1_1") (pintype "passive"))
    )
    (net (code "62") (name "Net-(LED7-PadA)") (class "Default")
      (node (ref "LED7") (pin "A") (pinfunction "A_A") (pintype "passive"))
      (node (ref "R6") (pin "1") (pinfunction "1_1") (pintype "passive"))
    )
    (net (code "63") (name "Net-(LED8-PadA)") (class "Default")
      (node (ref "LED8") (pin "A") (pinfunction "A_A") (pintype "passive"))
      (node (ref "R5") (pin "1") (pinfunction "1_1") (pintype "passive"))
    )
    (net (code "64") (name "Net-(OK1A-A)") (class "Default")
      (node (ref "OK1") (pin "1") (pinfunction "A_1") (pintype "passive"))
      (node (ref "R14") (pin "2") (pinfunction "2_2") (pintype "passive"))
    )
    (net (code "65") (name "Net-(OK1A-C)") (class "Default")
      (node (ref "OK1") (pin "2") (pinfunction "C_2") (pintype "passive"))
      (node (ref "X1") (pin "10") (pinfunction "F_10") (pintype "passive"))
    )
    (net (code "66") (name "Net-(OK1B-A)") (class "Default")
      (node (ref "OK1") (pin "3") (pinfunction "A_3") (pintype "passive"))
      (node (ref "R13") (pin "2") (pinfunction "2_2") (pintype "passive"))
    )
    (net (code "67") (name "Net-(OK1B-C)") (class "Default")
      (node (ref "OK1") (pin "4") (pinfunction "C_4") (pintype "passive"))
      (node (ref "X1") (pin "9") (pinfunction "F_9") (pintype "passive"))
    )
    (net (code "68") (name "Net-(OK2A-A)") (class "Default")
      (node (ref "OK2") (pin "1") (pinfunction "A_1") (pintype "passive"))
      (node (ref "R15") (pin "2") (pinfunction "2_2") (pintype "passive"))
    )
    (net (code "69") (name "Net-(OK2A-C)") (class "Default")
      (node (ref "OK2") (pin "2") (pinfunction "C_2") (pintype "passive"))
      (node (ref "X1") (pin "8") (pinfunction "F_8") (pintype "passive"))
    )
    (net (code "70") (name "Net-(OK2B-A)") (class "Default")
      (node (ref "OK2") (pin "3") (pinfunction "A_3") (pintype "passive"))
      (node (ref "R16") (pin "2") (pinfunction "2_2") (pintype "passive"))
    )
    (net (code "71") (name "Net-(OK2B-C)") (class "Default")
      (node (ref "OK2") (pin "4") (pinfunction "C_4") (pintype "passive"))
      (node (ref "X1") (pin "7") (pinfunction "F_7") (pintype "passive"))
    )
    (net (code "72") (name "Net-(OK3A-A)") (class "Default")
      (node (ref "OK3") (pin "1") (pinfunction "A_1") (pintype "passive"))
      (node (ref "R17") (pin "2") (pinfunction "2_2") (pintype "passive"))
    )
    (net (code "73") (name "Net-(OK3A-C)") (class "Default")
      (node (ref "OK3") (pin "2") (pinfunction "C_2") (pintype "passive"))
      (node (ref "X1") (pin "6") (pinfunction "F_6") (pintype "passive"))
    )
    (net (code "74") (name "Net-(OK3B-A)") (class "Default")
      (node (ref "OK3") (pin "3") (pinfunction "A_3") (pintype "passive"))
      (node (ref "R18") (pin "2") (pinfunction "2_2") (pintype "passive"))
    )
    (net (code "75") (name "Net-(OK3B-C)") (class "Default")
      (node (ref "OK3") (pin "4") (pinfunction "C_4") (pintype "passive"))
      (node (ref "X1") (pin "5") (pinfunction "F_5") (pintype "passive"))
    )
    (net (code "76") (name "Net-(OK4A-A)") (class "Default")
      (node (ref "OK4") (pin "1") (pinfunction "A_1") (pintype "passive"))
      (node (ref "R19") (pin "2") (pinfunction "2_2") (pintype "passive"))
    )
    (net (code "77") (name "Net-(OK4A-C)") (class "Default")
      (node (ref "OK4") (pin "2") (pinfunction "C_2") (pintype "passive"))
      (node (ref "X1") (pin "4") (pinfunction "F_4") (pintype "passive"))
    )
    (net (code "78") (name "Net-(OK4B-A)") (class "Default")
      (node (ref "OK4") (pin "3") (pinfunction "A_3") (pintype "passive"))
      (node (ref "R20") (pin "2") (pinfunction "2_2") (pintype "passive"))
    )
    (net (code "79") (name "Net-(OK4B-C)") (class "Default")
      (node (ref "OK4") (pin "4") (pinfunction "C_4") (pintype "passive"))
      (node (ref "X1") (pin "3") (pinfunction "F_3") (pintype "passive"))
    )
    (net (code "80") (name "Net-(S3-P)") (class "Default")
      (node (ref "S3") (pin "P$2") (pinfunction "P_P$2") (pintype "passive"))
      (node (ref "S3->A1") (pin "1") (pinfunction "1_1") (pintype "passive"))
    )
    (net (code "81") (name "Net-(U$7-P$2)") (class "Default")
      (node (ref "R4") (pin "1") (pinfunction "1_1") (pintype "passive"))
      (node (ref "U$7") (pin "A2") (pinfunction "P$2_A2") (pintype "bidirectional"))
    )
    (net (code "82") (name "Net-(U$7-P$3)") (class "Default")
      (node (ref "R3") (pin "1") (pinfunction "1_1") (pintype "passive"))
      (node (ref "U$7") (pin "A3") (pinfunction "P$3_A3") (pintype "bidirectional"))
    )
    (net (code "83") (name "unconnected-(GND-*D5-Pad5)") (class "Default")
      (node (ref "GND") (pin "5") (pinfunction "*D5_5") (pintype "bidirectional"))
    )
    (net (code "84") (name "unconnected-(GND-*D6-Pad6)") (class "Default")
      (node (ref "GND") (pin "6") (pinfunction "*D6_6") (pintype "bidirectional"))
    )
    (net (code "85") (name "unconnected-(GND-*D9-Pad9)") (class "Default")
      (node (ref "GND") (pin "9") (pinfunction "*D9_9") (pintype "bidirectional"))
    )
    (net (code "86") (name "unconnected-(GND-*D10-Pad10)") (class "Default")
      (node (ref "GND") (pin "10") (pinfunction "*D10_10") (pintype "bidirectional"))
    )
    (net (code "87") (name "unconnected-(GND-*D11-Pad11)") (class "Default")
      (node (ref "GND") (pin "11") (pinfunction "*D11_11") (pintype "bidirectional"))
    )
    (net (code "88") (name "unconnected-(GND-D4-Pad4)") (class "Default")
      (node (ref "GND") (pin "4") (pinfunction "D4_4") (pintype "bidirectional"))
    )
    (net (code "89") (name "unconnected-(GND-D7-Pad7)") (class "Default")
      (node (ref "GND") (pin "7") (pinfunction "D7_7") (pintype "bidirectional"))
    )
    (net (code "90") (name "unconnected-(GND-D8-Pad8)") (class "Default")
      (node (ref "GND") (pin "8") (pinfunction "D8_8") (pintype "bidirectional"))
    )
    (net (code "91") (name "unconnected-(GND-D12-Pad12)") (class "Default")
      (node (ref "GND") (pin "12") (pinfunction "D12_12") (pintype "bidirectional"))
    )
    (net (code "92") (name "unconnected-(GND-D13-Pad13)") (class "Default")
      (node (ref "GND") (pin "13") (pinfunction "D13_13") (pintype "bidirectional"))
    )
    (net (code "93") (name "unconnected-(GND-Pad3.3V)") (class "Default")
      (node (ref "GND") (pin "3.3V") (pinfunction "3.3V_3.3V") (pintype "bidirectional"))
    )
    (net (code "94") (name "unconnected-(GND-PadA0)") (class "Default")
      (node (ref "GND") (pin "A0") (pinfunction "A0_A0") (pintype "bidirectional"))
    )
    (net (code "95") (name "unconnected-(GND-PadA2)") (class "Default")
      (node (ref "GND") (pin "A2") (pinfunction "A2_A2") (pintype "bidirectional"))
    )
    (net (code "96") (name "unconnected-(GND-PadA3)") (class "Default")
      (node (ref "GND") (pin "A3") (pinfunction "A3_A3") (pintype "bidirectional"))
    )
    (net (code "97") (name "unconnected-(GND-PadAREF)") (class "Default")
      (node (ref "GND") (pin "AREF") (pinfunction "AREF_AREF") (pintype "bidirectional"))
    )
    (net (code "98") (name "unconnected-(GND-RX-Pad0)") (class "Default")
      (node (ref "GND") (pin "0") (pinfunction "RX_0") (pintype "bidirectional"))
    )
    (net (code "99") (name "unconnected-(GND-TX-Pad1)") (class "Default")
      (node (ref "GND") (pin "1") (pinfunction "TX_1") (pintype "bidirectional"))
    )
    (net (code "100") (name "unconnected-(IC2-INTA-Pad20)") (class "Default")
      (node (ref "IC2") (pin "20") (pinfunction "INTA_20") (pintype "output"))
    )
    (net (code "101") (name "unconnected-(IC2-INTB-Pad19)") (class "Default")
      (node (ref "IC2") (pin "19") (pinfunction "INTB_19") (pintype "output"))
    )
    (net (code "102") (name "unconnected-(K1B-O-PadO1)") (class "Default")
      (node (ref "K1") (pin "O1") (pinfunction "O_O1") (pintype "passive"))
    )
    (net (code "103") (name "unconnected-(K1C-O-PadO2)") (class "Default")
      (node (ref "K1") (pin "O2") (pinfunction "O_O2") (pintype "passive"))
    )
    (net (code "104") (name "unconnected-(K2B-O-PadO1)") (class "Default")
      (node (ref "K2") (pin "O1") (pinfunction "O_O1") (pintype "passive"))
    )
    (net (code "105") (name "unconnected-(K2C-O-PadO2)") (class "Default")
      (node (ref "K2") (pin "O2") (pinfunction "O_O2") (pintype "passive"))
    )
    (net (code "106") (name "unconnected-(K3B-O-PadO1)") (class "Default")
      (node (ref "K3") (pin "O1") (pinfunction "O_O1") (pintype "passive"))
    )
    (net (code "107") (name "unconnected-(K3C-O-PadO2)") (class "Default")
      (node (ref "K3") (pin "O2") (pinfunction "O_O2") (pintype "passive"))
    )
    (net (code "108") (name "unconnected-(K4B-O-PadO1)") (class "Default")
      (node (ref "K4") (pin "O1") (pinfunction "O_O1") (pintype "passive"))
    )
    (net (code "109") (name "unconnected-(K4C-O-PadO2)") (class "Default")
      (node (ref "K4") (pin "O2") (pinfunction "O_O2") (pintype "passive"))
    )
    (net (code "110") (name "unconnected-(K5B-O-PadO1)") (class "Default")
      (node (ref "K5") (pin "O1") (pinfunction "O_O1") (pintype "passive"))
    )
    (net (code "111") (name "unconnected-(K5C-O-PadO2)") (class "Default")
      (node (ref "K5") (pin "O2") (pinfunction "O_O2") (pintype "passive"))
    )
    (net (code "112") (name "unconnected-(K6B-O-PadO1)") (class "Default")
      (node (ref "K6") (pin "O1") (pinfunction "O_O1") (pintype "passive"))
    )
    (net (code "113") (name "unconnected-(K6C-O-PadO2)") (class "Default")
      (node (ref "K6") (pin "O2") (pinfunction "O_O2") (pintype "passive"))
    )
    (net (code "114") (name "unconnected-(K7B-O-PadO1)") (class "Default")
      (node (ref "K7") (pin "O1") (pinfunction "O_O1") (pintype "passive"))
    )
    (net (code "115") (name "unconnected-(K7C-O-PadO2)") (class "Default")
      (node (ref "K7") (pin "O2") (pinfunction "O_O2") (pintype "passive"))
    )
    (net (code "116") (name "unconnected-(K8B-O-PadO1)") (class "Default")
      (node (ref "K8") (pin "O1") (pinfunction "O_O1") (pintype "passive"))
    )
    (net (code "117") (name "unconnected-(K8C-O-PadO2)") (class "Default")
      (node (ref "K8") (pin "O2") (pinfunction "O_O2") (pintype "passive"))
    )
    (net (code "118") (name "unconnected-(SERIAL-Pad5)") (class "Default")
      (node (ref "SERIAL") (pin "5") (pinfunction "5_5") (pintype "passive"))
    )
    (net (code "119") (name "unconnected-(SERIAL-Pad6)") (class "Default")
      (node (ref "SERIAL") (pin "6") (pinfunction "6_6") (pintype "passive"))
    )
    (net (code "120") (name "unconnected-(SERIAL-Pad7)") (class "Default")
      (node (ref "SERIAL") (pin "7") (pinfunction "7_7") (pintype "passive"))
    )
    (net (code "121") (name "unconnected-(SERIAL-Pad8)") (class "Default")
      (node (ref "SERIAL") (pin "8") (pinfunction "8_8") (pintype "passive"))
    )
  )
)
